# hw2.net
KiCad netlist of a schematic drawn in EAGLE
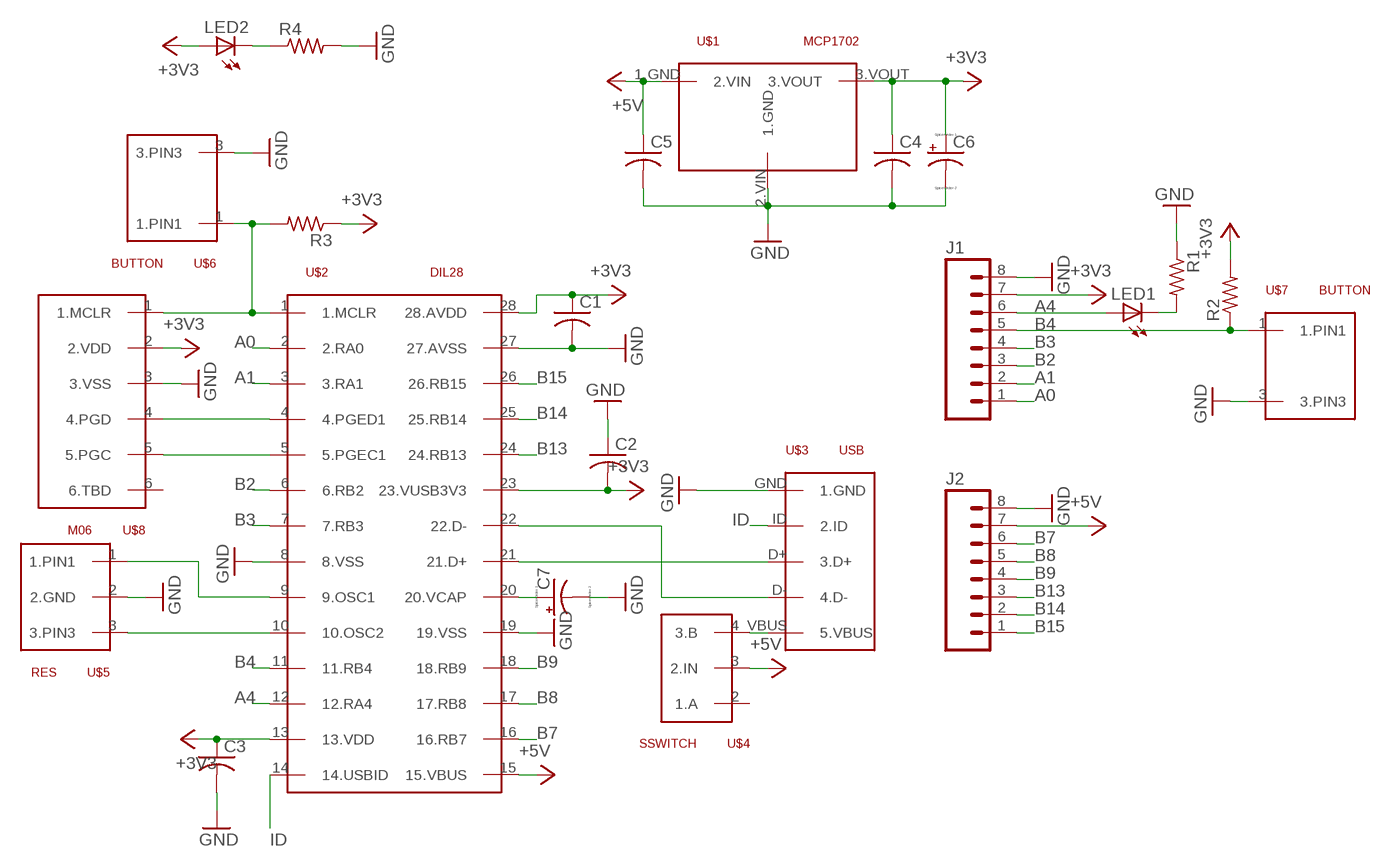
[diagram p0: schematic, sheet 1]

(export (version "E")
  (design (tool "Eeschema 10.0.6"))
  (components
    (comp (ref "C1")
      (value "C-US025-025X050")
      (footprint "eagle-import:C025-025X050")
      (libsource (lib "eagle-import") (part "C-US025-025X050"))
    )
    (comp (ref "C2")
      (value "C-US025-025X050")
      (footprint "eagle-import:C025-025X050")
      (libsource (lib "eagle-import") (part "C-US025-025X050"))
    )
    (comp (ref "C3")
      (value "C-US025-025X050")
      (footprint "eagle-import:C025-025X050")
      (libsource (lib "eagle-import") (part "C-US025-025X050"))
    )
    (comp (ref "C4")
      (value "C-US025-025X050")
      (footprint "eagle-import:C025-025X050")
      (libsource (lib "eagle-import") (part "C-US025-025X050"))
    )
    (comp (ref "C5")
      (value "C-US025-025X050")
      (footprint "eagle-import:C025-025X050")
      (libsource (lib "eagle-import") (part "C-US025-025X050"))
    )
    (comp (ref "C6")
      (value "CPOL-USTT2D4L")
      (footprint "eagle-import:TT2D4L")
      (libsource (lib "eagle-import") (part "CPOL-USTT2D4L"))
    )
    (comp (ref "C7")
      (value "CPOL-USTT2D4L")
      (footprint "eagle-import:TT2D4L")
      (libsource (lib "eagle-import") (part "CPOL-USTT2D4L"))
    )
    (comp (ref "J1")
      (value "M08")
      (footprint "eagle-import:1X08_ROUND")
      (libsource (lib "eagle-import") (part "M08"))
    )
    (comp (ref "J2")
      (value "M08")
      (footprint "eagle-import:1X08_ROUND")
      (libsource (lib "eagle-import") (part "M08"))
    )
    (comp (ref "LED1")
      (value "LED3MM")
      (footprint "eagle-import:LED3MM")
      (libsource (lib "eagle-import") (part "LED3MM"))
    )
    (comp (ref "LED2")
      (value "LED3MM")
      (footprint "eagle-import:LED3MM")
      (libsource (lib "eagle-import") (part "LED3MM"))
    )
    (comp (ref "R1")
      (value "R-US_0207/10")
      (footprint "eagle-import:0207_10")
      (libsource (lib "eagle-import") (part "R-US_0207/10"))
    )
    (comp (ref "R2")
      (value "R-US_0207/10")
      (footprint "eagle-import:0207_10")
      (libsource (lib "eagle-import") (part "R-US_0207/10"))
    )
    (comp (ref "R3")
      (value "R-US_0207/10")
      (footprint "eagle-import:0207_10")
      (libsource (lib "eagle-import") (part "R-US_0207/10"))
    )
    (comp (ref "R4")
      (value "R-US_0207/10")
      (footprint "eagle-import:0207_10")
      (libsource (lib "eagle-import") (part "R-US_0207/10"))
    )
    (comp (ref "U$1")
      (value "MCP1702")
      (footprint "eagle-import:TO92")
      (libsource (lib "eagle-import") (part "MCP1702"))
    )
    (comp (ref "U$2")
      (value "DIL28")
      (footprint "eagle-import:DIL28-3")
      (libsource (lib "eagle-import") (part "DIL28"))
    )
    (comp (ref "U$3")
      (value "USB")
      (footprint "eagle-import:USB-MB-H")
      (libsource (lib "eagle-import") (part "USB"))
    )
    (comp (ref "U$4")
      (value "SSWITCH")
      (footprint "eagle-import:SSWITCH")
      (libsource (lib "eagle-import") (part "SSWITCH"))
    )
    (comp (ref "U$5")
      (value "RES")
      (footprint "eagle-import:1X03")
      (libsource (lib "eagle-import") (part "RES"))
    )
    (comp (ref "U$6")
      (value "BUTTON")
      (footprint "eagle-import:BUTTON")
      (libsource (lib "eagle-import") (part "BUTTON"))
    )
    (comp (ref "U$7")
      (value "BUTTON")
      (footprint "eagle-import:BUTTON")
      (libsource (lib "eagle-import") (part "BUTTON"))
    )
    (comp (ref "U$8")
      (value "M06")
      (footprint "eagle-import:1X06")
      (libsource (lib "eagle-import") (part "M06"))
    )
  )
  (nets
    (net (code "1") (name "+3V3") (class "Default")
      (node (ref "C1") (pin "1") (pinfunction "1_1") (pintype "passive"))
      (node (ref "C2") (pin "2") (pinfunction "2_2") (pintype "passive"))
      (node (ref "C3") (pin "1") (pinfunction "1_1") (pintype "passive"))
      (node (ref "C4") (pin "1") (pinfunction "1_1") (pintype "passive"))
      (node (ref "C6") (pin "+") (pinfunction "+_+") (pintype "passive"))
      (node (ref "J1") (pin "7") (pinfunction "7_7") (pintype "passive"))
      (node (ref "LED2") (pin "A") (pinfunction "A_A") (pintype "passive"))
      (node (ref "R2") (pin "2") (pinfunction "2_2") (pintype "passive"))
      (node (ref "R3") (pin "1") (pinfunction "1_1") (pintype "passive"))
      (node (ref "U$1") (pin "3.VOUT") (pinfunction "3.VOUT_3.VOUT") (pintype "bidirectional"))
      (node (ref "U$2") (pin "13") (pinfunction "13.VDD_13") (pintype "bidirectional"))
      (node (ref "U$2") (pin "23") (pinfunction "23.VUSB3V3_23") (pintype "bidirectional"))
      (node (ref "U$2") (pin "28") (pinfunction "28.AVDD_28") (pintype "bidirectional"))
      (node (ref "U$8") (pin "2") (pinfunction "2.VDD_2") (pintype "bidirectional"))
    )
    (net (code "2") (name "+5V") (class "Default")
      (node (ref "C5") (pin "1") (pinfunction "1_1") (pintype "passive"))
      (node (ref "J2") (pin "7") (pinfunction "7_7") (pintype "passive"))
      (node (ref "U$1") (pin "1.GND") (pinfunction "2.VIN_1.GND") (pintype "bidirectional"))
      (node (ref "U$2") (pin "15") (pinfunction "15.VBUS_15") (pintype "bidirectional"))
      (node (ref "U$4") (pin "3") (pinfunction "2.IN_3") (pintype "bidirectional"))
    )
    (net (code "3") (name "/A0") (class "Default")
      (node (ref "J1") (pin "1") (pinfunction "1_1") (pintype "passive"))
      (node (ref "U$2") (pin "2") (pinfunction "2.RA0_2") (pintype "bidirectional"))
    )
    (net (code "4") (name "/A1") (class "Default")
      (node (ref "J1") (pin "2") (pinfunction "2_2") (pintype "passive"))
      (node (ref "U$2") (pin "3") (pinfunction "3.RA1_3") (pintype "bidirectional"))
    )
    (net (code "5") (name "/A4") (class "Default")
      (node (ref "J1") (pin "6") (pinfunction "6_6") (pintype "passive"))
      (node (ref "LED1") (pin "A") (pinfunction "A_A") (pintype "passive"))
      (node (ref "U$2") (pin "12") (pinfunction "12.RA4_12") (pintype "bidirectional"))
    )
    (net (code "6") (name "/B2") (class "Default")
      (node (ref "J1") (pin "3") (pinfunction "3_3") (pintype "passive"))
      (node (ref "U$2") (pin "6") (pinfunction "6.RB2_6") (pintype "bidirectional"))
    )
    (net (code "7") (name "/B3") (class "Default")
      (node (ref "J1") (pin "4") (pinfunction "4_4") (pintype "passive"))
      (node (ref "U$2") (pin "7") (pinfunction "7.RB3_7") (pintype "bidirectional"))
    )
    (net (code "8") (name "/B4") (class "Default")
      (node (ref "J1") (pin "5") (pinfunction "5_5") (pintype "passive"))
      (node (ref "R2") (pin "1") (pinfunction "1_1") (pintype "passive"))
      (node (ref "U$2") (pin "11") (pinfunction "11.RB4_11") (pintype "bidirectional"))
      (node (ref "U$7") (pin "1") (pinfunction "1.PIN1_1") (pintype "bidirectional"))
    )
    (net (code "9") (name "/B7") (class "Default")
      (node (ref "J2") (pin "6") (pinfunction "6_6") (pintype "passive"))
      (node (ref "U$2") (pin "16") (pinfunction "16.RB7_16") (pintype "bidirectional"))
    )
    (net (code "10") (name "/B8") (class "Default")
      (node (ref "J2") (pin "5") (pinfunction "5_5") (pintype "passive"))
      (node (ref "U$2") (pin "17") (pinfunction "17.RB8_17") (pintype "bidirectional"))
    )
    (net (code "11") (name "/B9") (class "Default")
      (node (ref "J2") (pin "4") (pinfunction "4_4") (pintype "passive"))
      (node (ref "U$2") (pin "18") (pinfunction "18.RB9_18") (pintype "bidirectional"))
    )
    (net (code "12") (name "/B13") (class "Default")
      (node (ref "J2") (pin "3") (pinfunction "3_3") (pintype "passive"))
      (node (ref "U$2") (pin "24") (pinfunction "24.RB13_24") (pintype "bidirectional"))
    )
    (net (code "13") (name "/B14") (class "Default")
      (node (ref "J2") (pin "2") (pinfunction "2_2") (pintype "passive"))
      (node (ref "U$2") (pin "25") (pinfunction "25.RB14_25") (pintype "bidirectional"))
    )
    (net (code "14") (name "/B15") (class "Default")
      (node (ref "J2") (pin "1") (pinfunction "1_1") (pintype "passive"))
      (node (ref "U$2") (pin "26") (pinfunction "26.RB15_26") (pintype "bidirectional"))
    )
    (net (code "15") (name "/ID") (class "Default")
      (node (ref "U$2") (pin "14") (pinfunction "14.USBID_14") (pintype "bidirectional"))
      (node (ref "U$3") (pin "ID") (pinfunction "2.ID_ID") (pintype "bidirectional"))
    )
    (net (code "16") (name "GND") (class "Default")
      (node (ref "C1") (pin "2") (pinfunction "2_2") (pintype "passive"))
      (node (ref "C2") (pin "1") (pinfunction "1_1") (pintype "passive"))
      (node (ref "C3") (pin "2") (pinfunction "2_2") (pintype "passive"))
      (node (ref "C4") (pin "2") (pinfunction "2_2") (pintype "passive"))
      (node (ref "C5") (pin "2") (pinfunction "2_2") (pintype "passive"))
      (node (ref "C6") (pin "-") (pinfunction "-_-") (pintype "passive"))
      (node (ref "C7") (pin "-") (pinfunction "-_-") (pintype "passive"))
      (node (ref "J1") (pin "8") (pinfunction "8_8") (pintype "passive"))
      (node (ref "J2") (pin "8") (pinfunction "8_8") (pintype "passive"))
      (node (ref "R1") (pin "1") (pinfunction "1_1") (pintype "passive"))
      (node (ref "R4") (pin "2") (pinfunction "2_2") (pintype "passive"))
      (node (ref "U$1") (pin "2.VIN") (pinfunction "1.GND_2.VIN") (pintype "bidirectional"))
      (node (ref "U$2") (pin "19") (pinfunction "19.VSS_19") (pintype "bidirectional"))
      (node (ref "U$2") (pin "27") (pinfunction "27.AVSS_27") (pintype "bidirectional"))
      (node (ref "U$2") (pin "8") (pinfunction "8.VSS_8") (pintype "bidirectional"))
      (node (ref "U$3") (pin "GND") (pinfunction "1.GND_GND") (pintype "bidirectional"))
      (node (ref "U$5") (pin "2") (pinfunction "2.GND_2") (pintype "bidirectional"))
      (node (ref "U$6") (pin "3") (pinfunction "3.PIN3_3") (pintype "bidirectional"))
      (node (ref "U$7") (pin "3") (pinfunction "3.PIN3_3") (pintype "bidirectional"))
      (node (ref "U$8") (pin "3") (pinfunction "3.VSS_3") (pintype "bidirectional"))
    )
    (net (code "17") (name "Net-(LED1-C)") (class "Default")
      (node (ref "LED1") (pin "K") (pinfunction "C_K") (pintype "passive"))
      (node (ref "R1") (pin "2") (pinfunction "2_2") (pintype "passive"))
    )
    (net (code "18") (name "Net-(LED2-C)") (class "Default")
      (node (ref "LED2") (pin "K") (pinfunction "C_K") (pintype "passive"))
      (node (ref "R4") (pin "1") (pinfunction "1_1") (pintype "passive"))
    )
    (net (code "19") (name "Net-(U$2-1.MCLR)") (class "Default")
      (node (ref "R3") (pin "2") (pinfunction "2_2") (pintype "passive"))
      (node (ref "U$2") (pin "1") (pinfunction "1.MCLR_1") (pintype "bidirectional"))
      (node (ref "U$6") (pin "1") (pinfunction "1.PIN1_1") (pintype "bidirectional"))
      (node (ref "U$8") (pin "1") (pinfunction "1.MCLR_1") (pintype "bidirectional"))
    )
    (net (code "20") (name "Net-(U$2-4.PGED1)") (class "Default")
      (node (ref "U$2") (pin "4") (pinfunction "4.PGED1_4") (pintype "bidirectional"))
      (node (ref "U$8") (pin "4") (pinfunction "4.PGD_4") (pintype "bidirectional"))
    )
    (net (code "21") (name "Net-(U$2-5.PGEC1)") (class "Default")
      (node (ref "U$2") (pin "5") (pinfunction "5.PGEC1_5") (pintype "bidirectional"))
      (node (ref "U$8") (pin "5") (pinfunction "5.PGC_5") (pintype "bidirectional"))
    )
    (net (code "22") (name "Net-(U$2-9.OSC1)") (class "Default")
      (node (ref "U$2") (pin "9") (pinfunction "9.OSC1_9") (pintype "bidirectional"))
      (node (ref "U$5") (pin "1") (pinfunction "1.PIN1_1") (pintype "bidirectional"))
    )
    (net (code "23") (name "Net-(U$2-10.OSC2)") (class "Default")
      (node (ref "U$2") (pin "10") (pinfunction "10.OSC2_10") (pintype "bidirectional"))
      (node (ref "U$5") (pin "3") (pinfunction "3.PIN3_3") (pintype "bidirectional"))
    )
    (net (code "24") (name "Net-(U$2-20.VCAP)") (class "Default")
      (node (ref "C7") (pin "+") (pinfunction "+_+") (pintype "passive"))
      (node (ref "U$2") (pin "20") (pinfunction "20.VCAP_20") (pintype "bidirectional"))
    )
    (net (code "25") (name "Net-(U$2-21.D+)") (class "Default")
      (node (ref "U$2") (pin "21") (pinfunction "21.D+_21") (pintype "bidirectional"))
      (node (ref "U$3") (pin "D+") (pinfunction "3.D+_D+") (pintype "bidirectional"))
    )
    (net (code "26") (name "Net-(U$2-22.D-)") (class "Default")
      (node (ref "U$2") (pin "22") (pinfunction "22.D-_22") (pintype "bidirectional"))
      (node (ref "U$3") (pin "D-") (pinfunction "4.D-_D-") (pintype "bidirectional"))
    )
    (net (code "27") (name "Net-(U$3-5.VBUS)") (class "Default")
      (node (ref "U$3") (pin "VBUS") (pinfunction "5.VBUS_VBUS") (pintype "bidirectional"))
      (node (ref "U$4") (pin "4") (pinfunction "3.B_4") (pintype "bidirectional"))
    )
    (net (code "28") (name "unconnected-(U$4-1.A-Pad2)") (class "Default")
      (node (ref "U$4") (pin "2") (pinfunction "1.A_2") (pintype "bidirectional"))
    )
    (net (code "29") (name "unconnected-(U$8-6.TBD-Pad6)") (class "Default")
      (node (ref "U$8") (pin "6") (pinfunction "6.TBD_6") (pintype "bidirectional"))
    )
  )
)
